# design.net
KiCad netlist of a schematic drawn in Altium Designer
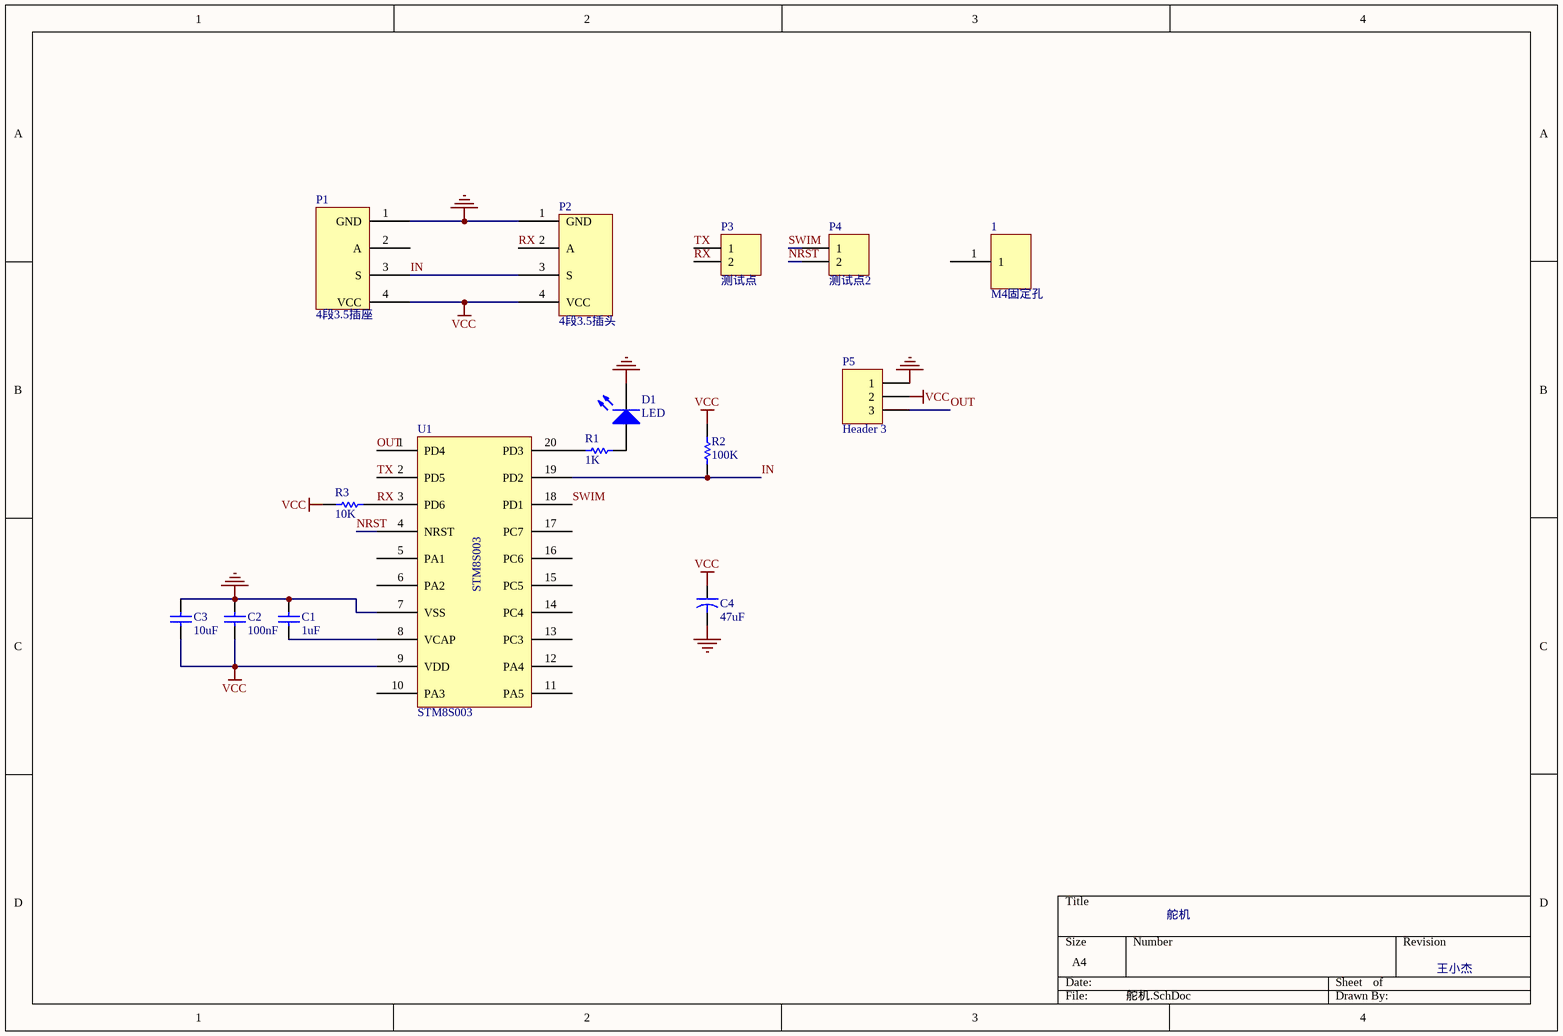
[diagram p0: 舵机.SchDoc]

(export (version "E")
  (design (tool "Eeschema 10.0.6"))
  (components
    (comp (ref "1") (value "M4固定孔") (footprint "M4固定孔") (libsource (lib "DDL6.30") (part "M4固定孔")))
    (comp (ref "C1")
      (value "1uF")
      (footprint "0603C")
      (description "Capacitor")
      (fields (field (name "PUBLISHER") "Altium Limited"))
      (libsource (lib "Miscellaneous Devices") (part "Cap"))
    )
    (comp (ref "C2")
      (value "100nF")
      (footprint "0603C")
      (description "Capacitor")
      (fields (field (name "PUBLISHER") "Altium Limited"))
      (libsource (lib "Miscellaneous Devices") (part "Cap"))
    )
    (comp (ref "C3")
      (value "10uF")
      (footprint "0603C")
      (description "Capacitor")
      (fields (field (name "PUBLISHER") "Altium Limited"))
      (libsource (lib "Miscellaneous Devices") (part "Cap"))
    )
    (comp (ref "C4")
      (value "47uF")
      (footprint "0805C")
      (description "Capacitor")
      (fields (field (name "PUBLISHER") "Altium Limited"))
      (libsource (lib "Miscellaneous Devices") (part "Cap2"))
    )
    (comp (ref "D1")
      (value "LED")
      (footprint "0603D")
      (description "Typical INFRARED GaAs LED")
      (fields (field (name "PUBLISHER") "Altium Limited"))
      (libsource (lib "Miscellaneous Devices") (part "LED0"))
    )
    (comp (ref "P1") (value "4段3.5插座") (footprint "4段3.5耳机贴片座") (libsource (lib "DDL6.30") (part "4段3.5插座")))
    (comp (ref "P2") (value "4段3.5插头") (footprint "4段3.5插头") (libsource (lib "DDL6.30") (part "4段3.5插头")))
    (comp (ref "P3")
      (value "测试点")
      (footprint "2SMT-2.54")
      (description "Header, 2-Pin")
      (fields (field (name "PUBLISHER") "Altium Limited"))
      (libsource (lib "Miscellaneous Connectors") (part "Header 2"))
    )
    (comp (ref "P4")
      (value "测试点2")
      (footprint "2SMT-2.54")
      (description "Header, 2-Pin")
      (fields (field (name "PUBLISHER") "Altium Limited"))
      (libsource (lib "Miscellaneous Connectors") (part "Header 2"))
    )
    (comp (ref "P5")
      (value "Header 3")
      (footprint "3pin弯脚")
      (description "Header, 3-Pin")
      (fields (field (name "PUBLISHER") "Altium Limited"))
      (libsource (lib "Miscellaneous Connectors") (part "Header 3"))
    )
    (comp (ref "R1")
      (value "1K")
      (footprint "0603R")
      (description "Resistor")
      (fields (field (name "PUBLISHER") "Altium Limited"))
      (libsource (lib "Miscellaneous Devices") (part "Res1"))
    )
    (comp (ref "R2")
      (value "100K")
      (footprint "0603R")
      (description "Resistor")
      (fields (field (name "PUBLISHER") "Altium Limited"))
      (libsource (lib "Miscellaneous Devices") (part "Res1"))
    )
    (comp (ref "R3")
      (value "10K")
      (footprint "0603R")
      (description "Resistor")
      (fields (field (name "PUBLISHER") "Altium Limited"))
      (libsource (lib "Miscellaneous Devices") (part "Res1"))
    )
    (comp (ref "U1") (value "STM8S003") (footprint "TSSOP20") (libsource (lib "DDL6.30") (part "STM8S003")))
  )
  (nets
    (net (code "1") (name "/IN") (class "Default")
      (node (ref "P1") (pin "3") (pinfunction "S_3") (pintype "passive"))
      (node (ref "P2") (pin "3") (pinfunction "S_3") (pintype "passive"))
      (node (ref "R2") (pin "1") (pinfunction "1_1") (pintype "passive"))
      (node (ref "U1") (pin "19") (pinfunction "PD2_19") (pintype "passive"))
    )
    (net (code "2") (name "/NRST") (class "Default")
      (node (ref "P4") (pin "2") (pinfunction "2_2") (pintype "passive"))
      (node (ref "U1") (pin "4") (pinfunction "NRST_4") (pintype "passive"))
    )
    (net (code "3") (name "/OUT") (class "Default")
      (node (ref "P5") (pin "3") (pinfunction "3_3") (pintype "passive"))
      (node (ref "U1") (pin "1") (pinfunction "PD4_1") (pintype "passive"))
    )
    (net (code "4") (name "/RX") (class "Default")
      (node (ref "P2") (pin "2") (pinfunction "A_2") (pintype "passive"))
      (node (ref "P3") (pin "2") (pinfunction "2_2") (pintype "passive"))
      (node (ref "R3") (pin "1") (pinfunction "1_1") (pintype "passive"))
      (node (ref "U1") (pin "3") (pinfunction "PD6_3") (pintype "passive"))
    )
    (net (code "5") (name "/SWIM") (class "Default")
      (node (ref "P4") (pin "1") (pinfunction "1_1") (pintype "passive"))
      (node (ref "U1") (pin "18") (pinfunction "PD1_18") (pintype "passive"))
    )
    (net (code "6") (name "/TX") (class "Default")
      (node (ref "P3") (pin "1") (pinfunction "1_1") (pintype "passive"))
      (node (ref "U1") (pin "2") (pinfunction "PD5_2") (pintype "passive"))
    )
    (net (code "7") (name "GND") (class "Default")
      (node (ref "C1") (pin "2") (pinfunction "2_2") (pintype "passive"))
      (node (ref "C2") (pin "2") (pinfunction "2_2") (pintype "passive"))
      (node (ref "C3") (pin "2") (pinfunction "2_2") (pintype "passive"))
      (node (ref "C4") (pin "2") (pinfunction "2_2") (pintype "passive"))
      (node (ref "D1") (pin "2") (pinfunction "K_2") (pintype "passive"))
      (node (ref "P1") (pin "1") (pinfunction "GND_1") (pintype "passive"))
      (node (ref "P2") (pin "1") (pinfunction "GND_1") (pintype "passive"))
      (node (ref "P5") (pin "1") (pinfunction "1_1") (pintype "passive"))
      (node (ref "U1") (pin "7") (pinfunction "VSS_7") (pintype "passive"))
    )
    (net (code "8") (name "Net-(D1-A)") (class "Default")
      (node (ref "D1") (pin "1") (pinfunction "A_1") (pintype "passive"))
      (node (ref "R1") (pin "2") (pinfunction "2_2") (pintype "passive"))
    )
    (net (code "9") (name "Net-(U1-PD3)") (class "Default")
      (node (ref "R1") (pin "1") (pinfunction "1_1") (pintype "passive"))
      (node (ref "U1") (pin "20") (pinfunction "PD3_20") (pintype "passive"))
    )
    (net (code "10") (name "Net-(U1-VCAP)") (class "Default")
      (node (ref "C1") (pin "1") (pinfunction "1_1") (pintype "passive"))
      (node (ref "U1") (pin "8") (pinfunction "VCAP_8") (pintype "passive"))
    )
    (net (code "11") (name "VCC") (class "Default")
      (node (ref "C2") (pin "1") (pinfunction "1_1") (pintype "passive"))
      (node (ref "C3") (pin "1") (pinfunction "1_1") (pintype "passive"))
      (node (ref "C4") (pin "1") (pinfunction "1_1") (pintype "passive"))
      (node (ref "P1") (pin "4") (pinfunction "VCC_4") (pintype "passive"))
      (node (ref "P2") (pin "4") (pinfunction "VCC_4") (pintype "passive"))
      (node (ref "P5") (pin "2") (pinfunction "2_2") (pintype "passive"))
      (node (ref "R2") (pin "2") (pinfunction "2_2") (pintype "passive"))
      (node (ref "R3") (pin "2") (pinfunction "2_2") (pintype "passive"))
      (node (ref "U1") (pin "9") (pinfunction "VDD_9") (pintype "passive"))
    )
    (net (code "12") (name "unconnected-(1-Pad1)") (class "Default")
      (node (ref "1") (pin "1") (pinfunction "1_1") (pintype "passive"))
    )
    (net (code "13") (name "unconnected-(P1-A-Pad2)") (class "Default")
      (node (ref "P1") (pin "2") (pinfunction "A_2") (pintype "passive"))
    )
    (net (code "14") (name "unconnected-(U1-PA1-Pad5)") (class "Default")
      (node (ref "U1") (pin "5") (pinfunction "PA1_5") (pintype "passive"))
    )
    (net (code "15") (name "unconnected-(U1-PA2-Pad6)") (class "Default")
      (node (ref "U1") (pin "6") (pinfunction "PA2_6") (pintype "passive"))
    )
    (net (code "16") (name "unconnected-(U1-PA3-Pad10)") (class "Default")
      (node (ref "U1") (pin "10") (pinfunction "PA3_10") (pintype "passive"))
    )
    (net (code "17") (name "unconnected-(U1-PA4-Pad12)") (class "Default")
      (node (ref "U1") (pin "12") (pinfunction "PA4_12") (pintype "passive"))
    )
    (net (code "18") (name "unconnected-(U1-PA5-Pad11)") (class "Default")
      (node (ref "U1") (pin "11") (pinfunction "PA5_11") (pintype "passive"))
    )
    (net (code "19") (name "unconnected-(U1-PC3-Pad13)") (class "Default")
      (node (ref "U1") (pin "13") (pinfunction "PC3_13") (pintype "passive"))
    )
    (net (code "20") (name "unconnected-(U1-PC4-Pad14)") (class "Default")
      (node (ref "U1") (pin "14") (pinfunction "PC4_14") (pintype "passive"))
    )
    (net (code "21") (name "unconnected-(U1-PC5-Pad15)") (class "Default")
      (node (ref "U1") (pin "15") (pinfunction "PC5_15") (pintype "passive"))
    )
    (net (code "22") (name "unconnected-(U1-PC6-Pad16)") (class "Default")
      (node (ref "U1") (pin "16") (pinfunction "PC6_16") (pintype "passive"))
    )
    (net (code "23") (name "unconnected-(U1-PC7-Pad17)") (class "Default")
      (node (ref "U1") (pin "17") (pinfunction "PC7_17") (pintype "passive"))
    )
  )
)
